# SensWear_Debug_DEBUG.net
KiCad netlist of a schematic drawn in Altium Designer
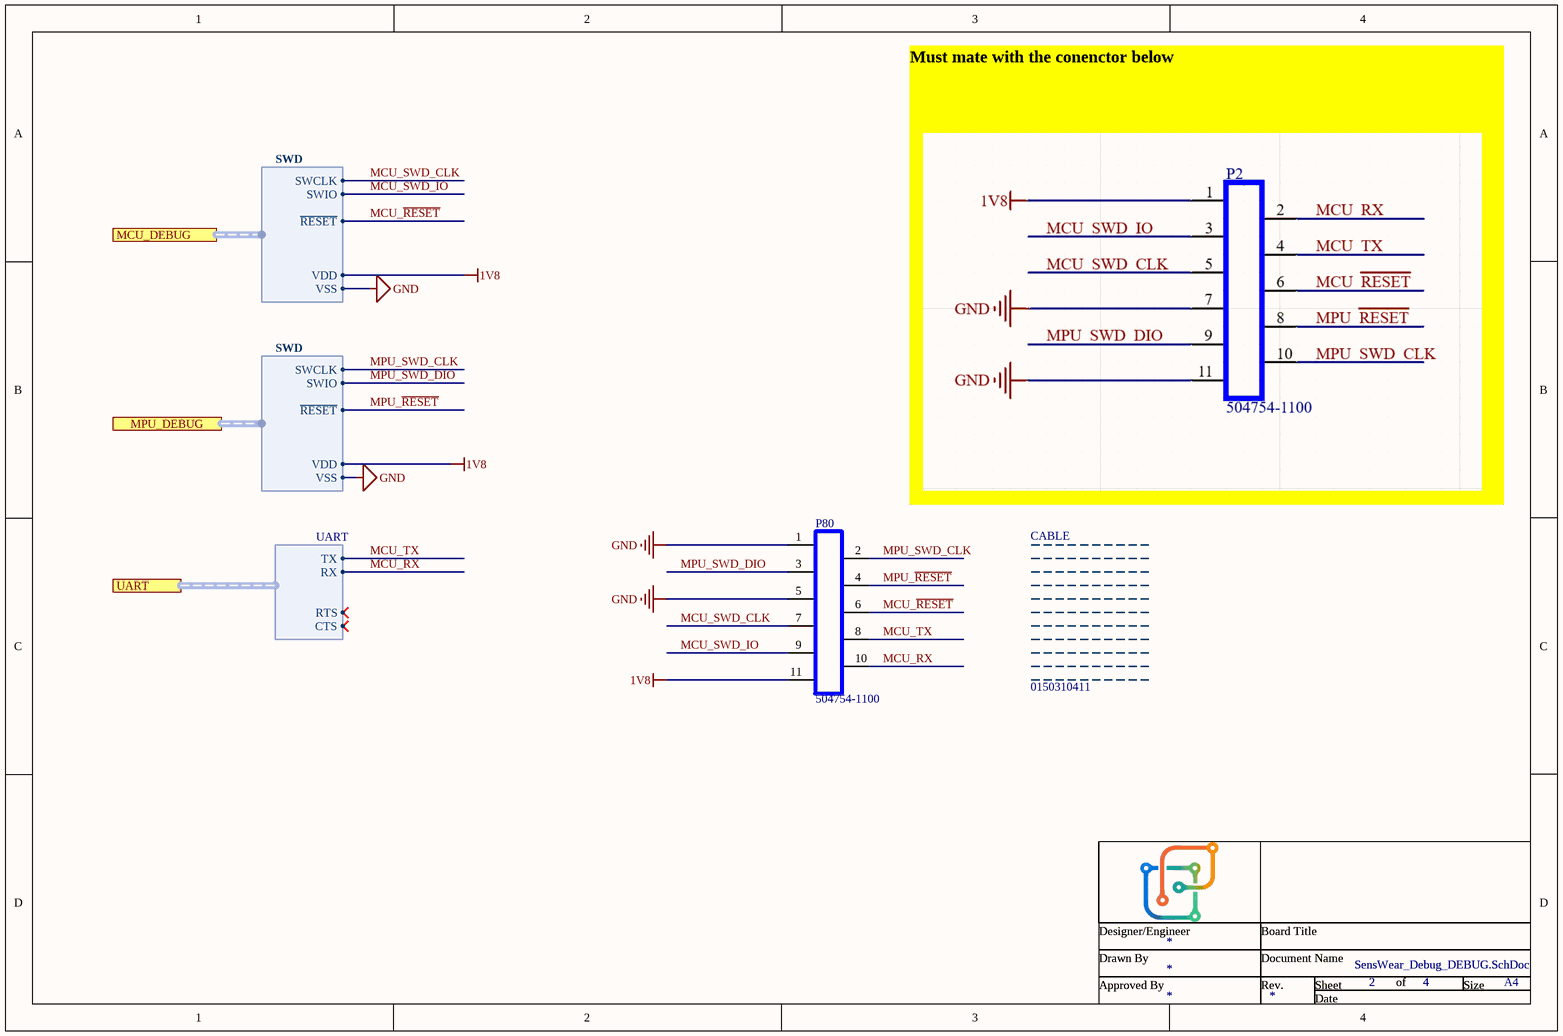
[diagram p0: SensWear_Debug_DEBUG.SchDoc]

(export (version "E")
  (design (tool "Eeschema 10.0.6"))
  (components
    (comp (ref "CABLE")
      (value "0150310411")
      (fields (field (name "MANUFACTURER") "Molex"))
      (libsource (lib "OpenRingComponents") (part "0150310411"))
    )
    (comp (ref "P80")
      (value "504754-1100")
      (footprint "5047541100")
      (description "Conn FFC/FPC Connector SKT 11 POS 0.3mm Solder RA SMD Easy-On™ T/R")
      (fields (field (name "MANUFACTURER") "Molex") (field (name "CHECKED") "FALSE"))
      (libsource (lib "Connectors") (part "504754-1100"))
    )
  )
  (nets
    (net (code "3") (name "/MCU_RX") (class "Default")
      (node (ref "P80") (pin "10") (pinfunction "10_10") (pintype "passive"))
    )
    (net (code "4") (name "/MCU_SWD_CLK") (class "Default")
      (node (ref "P80") (pin "7") (pinfunction "7_7") (pintype "passive"))
    )
    (net (code "5") (name "/MCU_SWD_IO") (class "Default")
      (node (ref "P80") (pin "9") (pinfunction "9_9") (pintype "passive"))
    )
    (net (code "6") (name "/MCU_TX") (class "Default")
      (node (ref "P80") (pin "8") (pinfunction "8_8") (pintype "passive"))
    )
    (net (code "7") (name "/MCU_~{RESET}") (class "Default")
      (node (ref "P80") (pin "6") (pinfunction "6_6") (pintype "passive"))
    )
    (net (code "8") (name "/MPU_SWD_CLK") (class "Default")
      (node (ref "P80") (pin "2") (pinfunction "2_2") (pintype "passive"))
    )
    (net (code "9") (name "/MPU_SWD_DIO") (class "Default")
      (node (ref "P80") (pin "3") (pinfunction "3_3") (pintype "passive"))
    )
    (net (code "10") (name "/MPU_~{RESET}") (class "Default")
      (node (ref "P80") (pin "4") (pinfunction "4_4") (pintype "passive"))
    )
    (net (code "13") (name "1V8") (class "Default")
      (node (ref "P80") (pin "11") (pinfunction "11_11") (pintype "passive"))
    )
    (net (code "14") (name "GND") (class "Default")
      (node (ref "P80") (pin "1") (pinfunction "1_1") (pintype "passive"))
      (node (ref "P80") (pin "5") (pinfunction "5_5") (pintype "passive"))
    )
  )
)
